# Qwiic_Solid_State_Relay.net
KiCad netlist of a schematic drawn in EAGLE
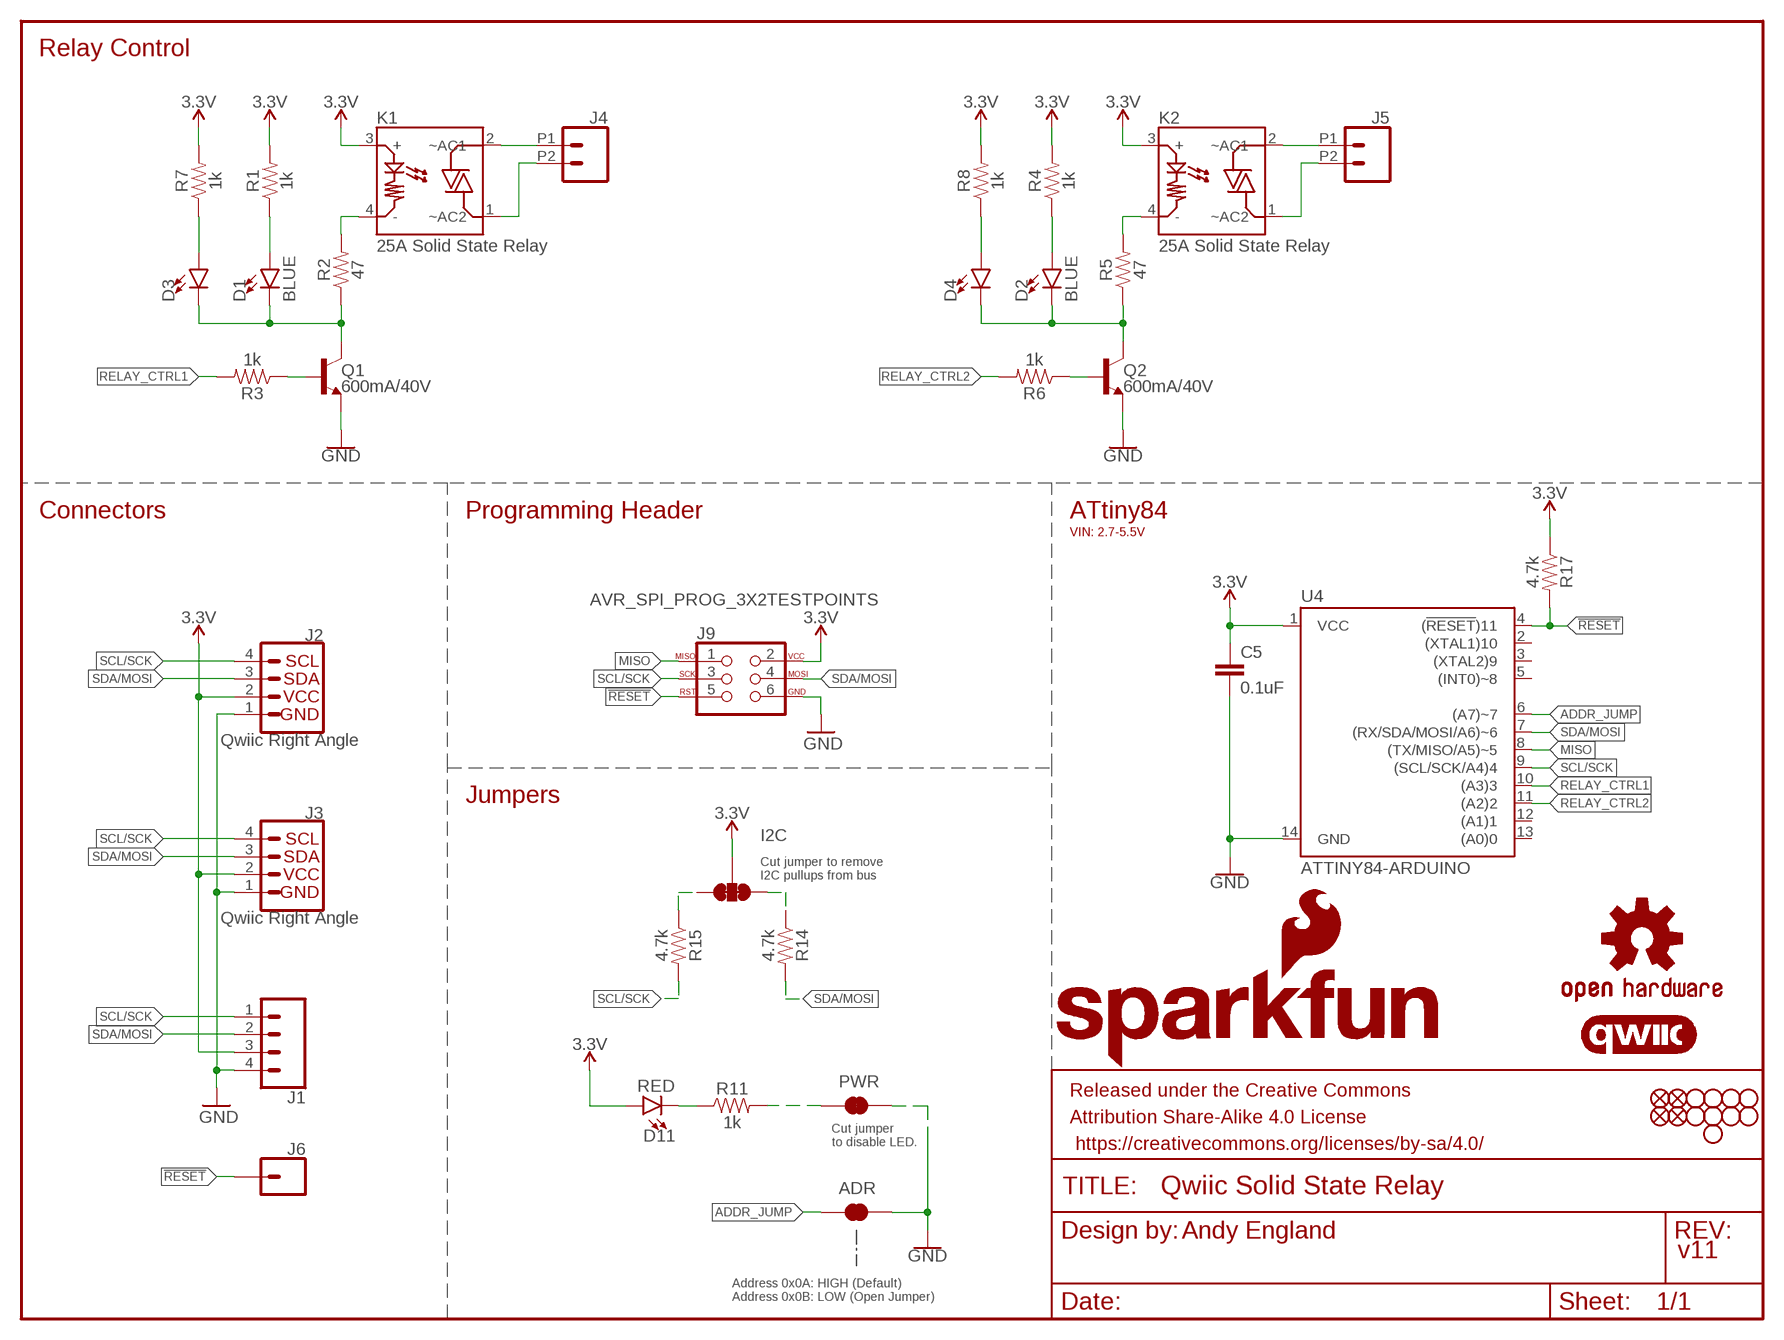
[diagram p0: schematic, sheet 1]

(export (version "E")
  (design (tool "Eeschema 10.0.6"))
  (components
    (comp (ref "ADR")
      (value "JUMPER-SMT_2_NC_TRACE_SILK")
      (footprint "eagle-import:SMT-JUMPER_2_NC_TRACE_SILK")
      (libsource (lib "eagle-import") (part "JUMPER-SMT_2_NC_TRACE_SILK"))
    )
    (comp (ref "C5")
      (value "0.1uF")
      (footprint "eagle-import:0603")
      (libsource (lib "eagle-import") (part "0.1UF-0603-25V-(+80/-20%)"))
    )
    (comp (ref "D1")
      (value "BLUE")
      (footprint "eagle-import:LED-0603")
      (libsource (lib "eagle-import") (part "LED-BLUE0603"))
    )
    (comp (ref "D2")
      (value "BLUE")
      (footprint "eagle-import:LED-0603")
      (libsource (lib "eagle-import") (part "LED-BLUE0603"))
    )
    (comp (ref "D3")
      (value "LED5MM")
      (footprint "eagle-import:LED_5MM")
      (libsource (lib "eagle-import") (part "LED5MM"))
    )
    (comp (ref "D4")
      (value "LED5MM")
      (footprint "eagle-import:LED_5MM")
      (libsource (lib "eagle-import") (part "LED5MM"))
    )
    (comp (ref "D11")
      (value "RED")
      (footprint "eagle-import:LED-0603")
      (libsource (lib "eagle-import") (part "LED-RED0603"))
    )
    (comp (ref "FD1")
      (value "FIDUCIAL1X2")
      (footprint "eagle-import:FIDUCIAL-1X2")
      (libsource (lib "eagle-import") (part "FIDUCIAL1X2"))
    )
    (comp (ref "FD2")
      (value "FIDUCIAL1X2")
      (footprint "eagle-import:FIDUCIAL-1X2")
      (libsource (lib "eagle-import") (part "FIDUCIAL1X2"))
    )
    (comp (ref "FD3")
      (value "FIDUCIAL1X2")
      (footprint "eagle-import:FIDUCIAL-1X2")
      (libsource (lib "eagle-import") (part "FIDUCIAL1X2"))
    )
    (comp (ref "FD4")
      (value "FIDUCIAL1X2")
      (footprint "eagle-import:FIDUCIAL-1X2")
      (libsource (lib "eagle-import") (part "FIDUCIAL1X2"))
    )
    (comp (ref "FRAME1")
      (value "FRAME-LETTER")
      (footprint "eagle-import:CREATIVE_COMMONS")
      (libsource (lib "eagle-import") (part "FRAME-LETTER"))
    )
    (comp (ref "I2C")
      (value "JUMPER-SMT_3_2-NC_TRACE_SILK")
      (footprint "eagle-import:SMT-JUMPER_3_2-NC_TRACE_SILK")
      (libsource (lib "eagle-import") (part "JUMPER-SMT_3_2-NC_TRACE_SILK"))
    )
    (comp (ref "J1")
      (value "CONN_041X04_NO_SILK")
      (footprint "eagle-import:1X04_NO_SILK")
      (libsource (lib "eagle-import") (part "CONN_041X04_NO_SILK"))
    )
    (comp (ref "J2")
      (value "Qwiic Right Angle")
      (footprint "eagle-import:JST04_1MM_RA")
      (libsource (lib "eagle-import") (part "I2C_STANDARDQWIIC"))
    )
    (comp (ref "J3")
      (value "Qwiic Right Angle")
      (footprint "eagle-import:JST04_1MM_RA")
      (libsource (lib "eagle-import") (part "I2C_STANDARDQWIIC"))
    )
    (comp (ref "J4")
      (value "CONN_02SCREWTERMINAL-6.35MM-2")
      (footprint "eagle-import:1X02_6.35_SCREWTERM")
      (libsource (lib "eagle-import") (part "CONN_02SCREWTERMINAL-6.35MM-2"))
    )
    (comp (ref "J5")
      (value "CONN_02SCREWTERMINAL-6.35MM-2")
      (footprint "eagle-import:1X02_6.35_SCREWTERM")
      (libsource (lib "eagle-import") (part "CONN_02SCREWTERMINAL-6.35MM-2"))
    )
    (comp (ref "J6")
      (value "CONN_01PTH_NO_SILK_YES_STOP")
      (footprint "eagle-import:1X01_NO_SILK")
      (libsource (lib "eagle-import") (part "CONN_01PTH_NO_SILK_YES_STOP"))
    )
    (comp (ref "J9")
      (value "AVR_SPI_PROG_3X2TESTPOINTS")
      (footprint "eagle-import:2X3_TEST_POINTS")
      (libsource (lib "eagle-import") (part "AVR_SPI_PROG_3X2TESTPOINTS"))
    )
    (comp (ref "JP1")
      (value "STAND-OFF")
      (footprint "eagle-import:STAND-OFF")
      (libsource (lib "eagle-import") (part "STAND-OFF"))
    )
    (comp (ref "JP2")
      (value "STAND-OFF")
      (footprint "eagle-import:STAND-OFF")
      (libsource (lib "eagle-import") (part "STAND-OFF"))
    )
    (comp (ref "JP3")
      (value "STAND-OFF")
      (footprint "eagle-import:STAND-OFF")
      (libsource (lib "eagle-import") (part "STAND-OFF"))
    )
    (comp (ref "JP4")
      (value "STAND-OFF")
      (footprint "eagle-import:STAND-OFF")
      (libsource (lib "eagle-import") (part "STAND-OFF"))
    )
    (comp (ref "JP5")
      (value "STAND-OFF")
      (footprint "eagle-import:STAND-OFF")
      (libsource (lib "eagle-import") (part "STAND-OFF"))
    )
    (comp (ref "JP6")
      (value "STAND-OFF")
      (footprint "eagle-import:STAND-OFF")
      (libsource (lib "eagle-import") (part "STAND-OFF"))
    )
    (comp (ref "JP7")
      (value "STAND-OFF")
      (footprint "eagle-import:STAND-OFF")
      (libsource (lib "eagle-import") (part "STAND-OFF"))
    )
    (comp (ref "JP8")
      (value "STAND-OFF")
      (footprint "eagle-import:STAND-OFF")
      (libsource (lib "eagle-import") (part "STAND-OFF"))
    )
    (comp (ref "JP10")
      (value "STAND-OFF")
      (footprint "eagle-import:STAND-OFF")
      (libsource (lib "eagle-import") (part "STAND-OFF"))
    )
    (comp (ref "K1")
      (value "25A Solid State Relay")
      (footprint "eagle-import:PTH_SOLIDSTATERELAY")
      (libsource (lib "eagle-import") (part "SIP_SOLIDSTATERELAY"))
    )
    (comp (ref "K2")
      (value "25A Solid State Relay")
      (footprint "eagle-import:PTH_SOLIDSTATERELAY")
      (libsource (lib "eagle-import") (part "SIP_SOLIDSTATERELAY"))
    )
    (comp (ref "LOGO1")
      (value "SFE_LOGO_NAME_FLAME.2_INCH")
      (footprint "eagle-import:SFE_LOGO_NAME_FLAME_.2")
      (libsource (lib "eagle-import") (part "SFE_LOGO_NAME_FLAME.2_INCH"))
    )
    (comp (ref "LOGO2")
      (value "OSHW-LOGOS")
      (footprint "eagle-import:OSHW-LOGO-S")
      (libsource (lib "eagle-import") (part "OSHW-LOGOS"))
    )
    (comp (ref "LOGO3")
      (value "SFE_LOGO_NAME_FLAME.3_INCH")
      (footprint "eagle-import:SFE_LOGO_NAME_FLAME_.3")
      (libsource (lib "eagle-import") (part "SFE_LOGO_NAME_FLAME.3_INCH"))
    )
    (comp (ref "LOGO4")
      (value "QWIIC_LOGO_5MM")
      (footprint "eagle-import:QWIIC_5MM")
      (libsource (lib "eagle-import") (part "QWIIC_LOGO_5MM"))
    )
    (comp (ref "PWR")
      (value "JUMPER-SMT_2_NC_TRACE_SILK")
      (footprint "eagle-import:SMT-JUMPER_2_NC_TRACE_SILK")
      (libsource (lib "eagle-import") (part "JUMPER-SMT_2_NC_TRACE_SILK"))
    )
    (comp (ref "Q1")
      (value "600mA/40V")
      (footprint "eagle-import:SOT23-3")
      (libsource (lib "eagle-import") (part "TRANS_NPN-MMBT2222AL"))
    )
    (comp (ref "Q2")
      (value "600mA/40V")
      (footprint "eagle-import:SOT23-3")
      (libsource (lib "eagle-import") (part "TRANS_NPN-MMBT2222AL"))
    )
    (comp (ref "R1")
      (value "1k")
      (footprint "eagle-import:0603")
      (libsource (lib "eagle-import") (part "1KOHM-0603-1/10W-1%"))
    )
    (comp (ref "R2")
      (value "47")
      (footprint "eagle-import:0603")
      (libsource (lib "eagle-import") (part "47OHM-0603-1/10W-1%"))
    )
    (comp (ref "R3")
      (value "1k")
      (footprint "eagle-import:0603")
      (libsource (lib "eagle-import") (part "1KOHM-0603-1/10W-1%"))
    )
    (comp (ref "R4")
      (value "1k")
      (footprint "eagle-import:0603")
      (libsource (lib "eagle-import") (part "1KOHM-0603-1/10W-1%"))
    )
    (comp (ref "R5")
      (value "47")
      (footprint "eagle-import:0603")
      (libsource (lib "eagle-import") (part "47OHM-0603-1/10W-1%"))
    )
    (comp (ref "R6")
      (value "1k")
      (footprint "eagle-import:0603")
      (libsource (lib "eagle-import") (part "1KOHM-0603-1/10W-1%"))
    )
    (comp (ref "R7")
      (value "1k")
      (footprint "eagle-import:0603")
      (libsource (lib "eagle-import") (part "1KOHM-0603-1/10W-1%"))
    )
    (comp (ref "R8")
      (value "1k")
      (footprint "eagle-import:0603")
      (libsource (lib "eagle-import") (part "1KOHM-0603-1/10W-1%"))
    )
    (comp (ref "R11")
      (value "1k")
      (footprint "eagle-import:0603")
      (libsource (lib "eagle-import") (part "1KOHM-0603-1/10W-1%"))
    )
    (comp (ref "R14")
      (value "4.7k")
      (footprint "eagle-import:0603")
      (libsource (lib "eagle-import") (part "4.7KOHM-0603-1/10W-1%"))
    )
    (comp (ref "R15")
      (value "4.7k")
      (footprint "eagle-import:0603")
      (libsource (lib "eagle-import") (part "4.7KOHM-0603-1/10W-1%"))
    )
    (comp (ref "R17")
      (value "4.7k")
      (footprint "eagle-import:0603")
      (libsource (lib "eagle-import") (part "4.7KOHM-0603-1/10W-1%"))
    )
    (comp (ref "U4")
      (value "ATTINY84-ARDUINO")
      (footprint "eagle-import:SO14")
      (libsource (lib "eagle-import") (part "ATTINY84-ARDUINO"))
    )
  )
  (nets
    (net (code "1") (name "/~{RESET}") (class "Default")
      (node (ref "J6") (pin "1") (pinfunction "1_1") (pintype "passive"))
      (node (ref "J9") (pin "5") (pinfunction "5_5") (pintype "passive"))
      (node (ref "R17") (pin "2") (pinfunction "2_2") (pintype "passive"))
      (node (ref "U4") (pin "4") (pinfunction "(~{RESET})11_4") (pintype "bidirectional"))
    )
    (net (code "2") (name "3.3V") (class "Default")
      (node (ref "C5") (pin "1") (pinfunction "1_1") (pintype "passive"))
      (node (ref "D11") (pin "A") (pinfunction "A_A") (pintype "passive"))
      (node (ref "I2C") (pin "2") (pinfunction "2_2") (pintype "passive"))
      (node (ref "J1") (pin "3") (pinfunction "3_3") (pintype "passive"))
      (node (ref "J2") (pin "2") (pinfunction "2_2") (pintype "power_in"))
      (node (ref "J3") (pin "2") (pinfunction "2_2") (pintype "power_in"))
      (node (ref "J9") (pin "2") (pinfunction "2_2") (pintype "passive"))
      (node (ref "K1") (pin "3") (pinfunction "+_3") (pintype "bidirectional"))
      (node (ref "K2") (pin "3") (pinfunction "+_3") (pintype "bidirectional"))
      (node (ref "R1") (pin "2") (pinfunction "2_2") (pintype "passive"))
      (node (ref "R17") (pin "1") (pinfunction "1_1") (pintype "passive"))
      (node (ref "R4") (pin "2") (pinfunction "2_2") (pintype "passive"))
      (node (ref "R7") (pin "2") (pinfunction "2_2") (pintype "passive"))
      (node (ref "R8") (pin "2") (pinfunction "2_2") (pintype "passive"))
      (node (ref "U4") (pin "1") (pinfunction "VCC_1") (pintype "bidirectional"))
    )
    (net (code "3") (name "ADDR_JUMP") (class "Default")
      (node (ref "ADR") (pin "1") (pinfunction "1_1") (pintype "passive"))
      (node (ref "U4") (pin "6") (pinfunction "(A7)~{7}_6") (pintype "bidirectional"))
    )
    (net (code "4") (name "GND") (class "Default")
      (node (ref "ADR") (pin "2") (pinfunction "2_2") (pintype "passive"))
      (node (ref "C5") (pin "2") (pinfunction "2_2") (pintype "passive"))
      (node (ref "J1") (pin "4") (pinfunction "4_4") (pintype "passive"))
      (node (ref "J2") (pin "1") (pinfunction "1_1") (pintype "power_in"))
      (node (ref "J3") (pin "1") (pinfunction "1_1") (pintype "power_in"))
      (node (ref "J9") (pin "6") (pinfunction "6_6") (pintype "passive"))
      (node (ref "PWR") (pin "1") (pinfunction "1_1") (pintype "passive"))
      (node (ref "Q1") (pin "2") (pinfunction "E_2") (pintype "passive"))
      (node (ref "Q2") (pin "2") (pinfunction "E_2") (pintype "passive"))
      (node (ref "U4") (pin "14") (pinfunction "GND_14") (pintype "bidirectional"))
    )
    (net (code "5") (name "MISO") (class "Default")
      (node (ref "J9") (pin "1") (pinfunction "1_1") (pintype "passive"))
      (node (ref "U4") (pin "8") (pinfunction "(TX/MISO/A5)~{5}_8") (pintype "bidirectional"))
    )
    (net (code "6") (name "Net-(D1-PadA)") (class "Default")
      (node (ref "D1") (pin "A") (pinfunction "A_A") (pintype "passive"))
      (node (ref "R1") (pin "1") (pinfunction "1_1") (pintype "passive"))
    )
    (net (code "7") (name "Net-(D2-PadA)") (class "Default")
      (node (ref "D2") (pin "A") (pinfunction "A_A") (pintype "passive"))
      (node (ref "R4") (pin "1") (pinfunction "1_1") (pintype "passive"))
    )
    (net (code "8") (name "Net-(D3-C)") (class "Default")
      (node (ref "D1") (pin "C") (pinfunction "C_C") (pintype "passive"))
      (node (ref "D3") (pin "K") (pinfunction "C_K") (pintype "passive"))
      (node (ref "Q1") (pin "3") (pinfunction "C_3") (pintype "passive"))
      (node (ref "R2") (pin "1") (pinfunction "1_1") (pintype "passive"))
    )
    (net (code "9") (name "Net-(D3-PadA)") (class "Default")
      (node (ref "D3") (pin "A") (pinfunction "A_A") (pintype "passive"))
      (node (ref "R7") (pin "1") (pinfunction "1_1") (pintype "passive"))
    )
    (net (code "10") (name "Net-(D4-C)") (class "Default")
      (node (ref "D2") (pin "C") (pinfunction "C_C") (pintype "passive"))
      (node (ref "D4") (pin "K") (pinfunction "C_K") (pintype "passive"))
      (node (ref "Q2") (pin "3") (pinfunction "C_3") (pintype "passive"))
      (node (ref "R5") (pin "1") (pinfunction "1_1") (pintype "passive"))
    )
    (net (code "11") (name "Net-(D4-PadA)") (class "Default")
      (node (ref "D4") (pin "A") (pinfunction "A_A") (pintype "passive"))
      (node (ref "R8") (pin "1") (pinfunction "1_1") (pintype "passive"))
    )
    (net (code "12") (name "Net-(D11-PadC)") (class "Default")
      (node (ref "D11") (pin "C") (pinfunction "C_C") (pintype "passive"))
      (node (ref "R11") (pin "1") (pinfunction "1_1") (pintype "passive"))
    )
    (net (code "13") (name "Net-(I2C-Pad1)") (class "Default")
      (node (ref "I2C") (pin "1") (pinfunction "1_1") (pintype "passive"))
      (node (ref "R14") (pin "1") (pinfunction "1_1") (pintype "passive"))
    )
    (net (code "14") (name "Net-(I2C-Pad3)") (class "Default")
      (node (ref "I2C") (pin "3") (pinfunction "3_3") (pintype "passive"))
      (node (ref "R15") (pin "1") (pinfunction "1_1") (pintype "passive"))
    )
    (net (code "15") (name "Net-(J4-1)") (class "Default")
      (node (ref "J4") (pin "P2") (pinfunction "1_P2") (pintype "passive"))
      (node (ref "K1") (pin "1") (pinfunction "~{AC2}_1") (pintype "bidirectional"))
    )
    (net (code "16") (name "Net-(J4-2)") (class "Default")
      (node (ref "J4") (pin "P1") (pinfunction "2_P1") (pintype "passive"))
      (node (ref "K1") (pin "2") (pinfunction "~{AC1}_2") (pintype "bidirectional"))
    )
    (net (code "17") (name "Net-(J5-1)") (class "Default")
      (node (ref "J5") (pin "P2") (pinfunction "1_P2") (pintype "passive"))
      (node (ref "K2") (pin "1") (pinfunction "~{AC2}_1") (pintype "bidirectional"))
    )
    (net (code "18") (name "Net-(J5-2)") (class "Default")
      (node (ref "J5") (pin "P1") (pinfunction "2_P1") (pintype "passive"))
      (node (ref "K2") (pin "2") (pinfunction "~{AC1}_2") (pintype "bidirectional"))
    )
    (net (code "19") (name "Net-(K1--)") (class "Default")
      (node (ref "K1") (pin "4") (pinfunction "-_4") (pintype "bidirectional"))
      (node (ref "R2") (pin "2") (pinfunction "2_2") (pintype "passive"))
    )
    (net (code "20") (name "Net-(K2--)") (class "Default")
      (node (ref "K2") (pin "4") (pinfunction "-_4") (pintype "bidirectional"))
      (node (ref "R5") (pin "2") (pinfunction "2_2") (pintype "passive"))
    )
    (net (code "21") (name "Net-(PWR-Pad2)") (class "Default")
      (node (ref "PWR") (pin "2") (pinfunction "2_2") (pintype "passive"))
      (node (ref "R11") (pin "2") (pinfunction "2_2") (pintype "passive"))
    )
    (net (code "22") (name "Net-(Q1-B)") (class "Default")
      (node (ref "Q1") (pin "1") (pinfunction "B_1") (pintype "passive"))
      (node (ref "R3") (pin "1") (pinfunction "1_1") (pintype "passive"))
    )
    (net (code "23") (name "Net-(Q2-B)") (class "Default")
      (node (ref "Q2") (pin "1") (pinfunction "B_1") (pintype "passive"))
      (node (ref "R6") (pin "1") (pinfunction "1_1") (pintype "passive"))
    )
    (net (code "24") (name "RELAY_CTRL1") (class "Default")
      (node (ref "R3") (pin "2") (pinfunction "2_2") (pintype "passive"))
      (node (ref "U4") (pin "10") (pinfunction "(A3)3_10") (pintype "bidirectional"))
    )
    (net (code "25") (name "RELAY_CTRL2") (class "Default")
      (node (ref "R6") (pin "2") (pinfunction "2_2") (pintype "passive"))
      (node (ref "U4") (pin "11") (pinfunction "(A2)2_11") (pintype "bidirectional"))
    )
    (net (code "26") (name "SCL{slash}SCK") (class "Default")
      (node (ref "J1") (pin "1") (pinfunction "1_1") (pintype "passive"))
      (node (ref "J2") (pin "4") (pinfunction "4_4") (pintype "passive"))
      (node (ref "J3") (pin "4") (pinfunction "4_4") (pintype "passive"))
      (node (ref "J9") (pin "3") (pinfunction "3_3") (pintype "passive"))
      (node (ref "R15") (pin "2") (pinfunction "2_2") (pintype "passive"))
      (node (ref "U4") (pin "9") (pinfunction "(SCL/SCK/A4)4_9") (pintype "bidirectional"))
    )
    (net (code "27") (name "SDA{slash}MOSI") (class "Default")
      (node (ref "J1") (pin "2") (pinfunction "2_2") (pintype "passive"))
      (node (ref "J2") (pin "3") (pinfunction "3_3") (pintype "passive"))
      (node (ref "J3") (pin "3") (pinfunction "3_3") (pintype "passive"))
      (node (ref "J9") (pin "4") (pinfunction "4_4") (pintype "passive"))
      (node (ref "R14") (pin "2") (pinfunction "2_2") (pintype "passive"))
      (node (ref "U4") (pin "7") (pinfunction "(RX/SDA/MOSI/A6)~{6}_7") (pintype "bidirectional"))
    )
    (net (code "28") (name "unconnected-(U4-(A0)0-Pad13)") (class "Default")
      (node (ref "U4") (pin "13") (pinfunction "(A0)0_13") (pintype "bidirectional"))
    )
    (net (code "29") (name "unconnected-(U4-(A1)1-Pad12)") (class "Default")
      (node (ref "U4") (pin "12") (pinfunction "(A1)1_12") (pintype "bidirectional"))
    )
    (net (code "30") (name "unconnected-(U4-(INT0)~{8}-Pad5)") (class "Default")
      (node (ref "U4") (pin "5") (pinfunction "(INT0)~{8}_5") (pintype "bidirectional"))
    )
    (net (code "31") (name "unconnected-(U4-(XTAL1)10-Pad2)") (class "Default")
      (node (ref "U4") (pin "2") (pinfunction "(XTAL1)10_2") (pintype "bidirectional"))
    )
    (net (code "32") (name "unconnected-(U4-(XTAL2)9-Pad3)") (class "Default")
      (node (ref "U4") (pin "3") (pinfunction "(XTAL2)9_3") (pintype "bidirectional"))
    )
  )
)
